# charger_v4.net
KiCad netlist of a schematic drawn in EAGLE
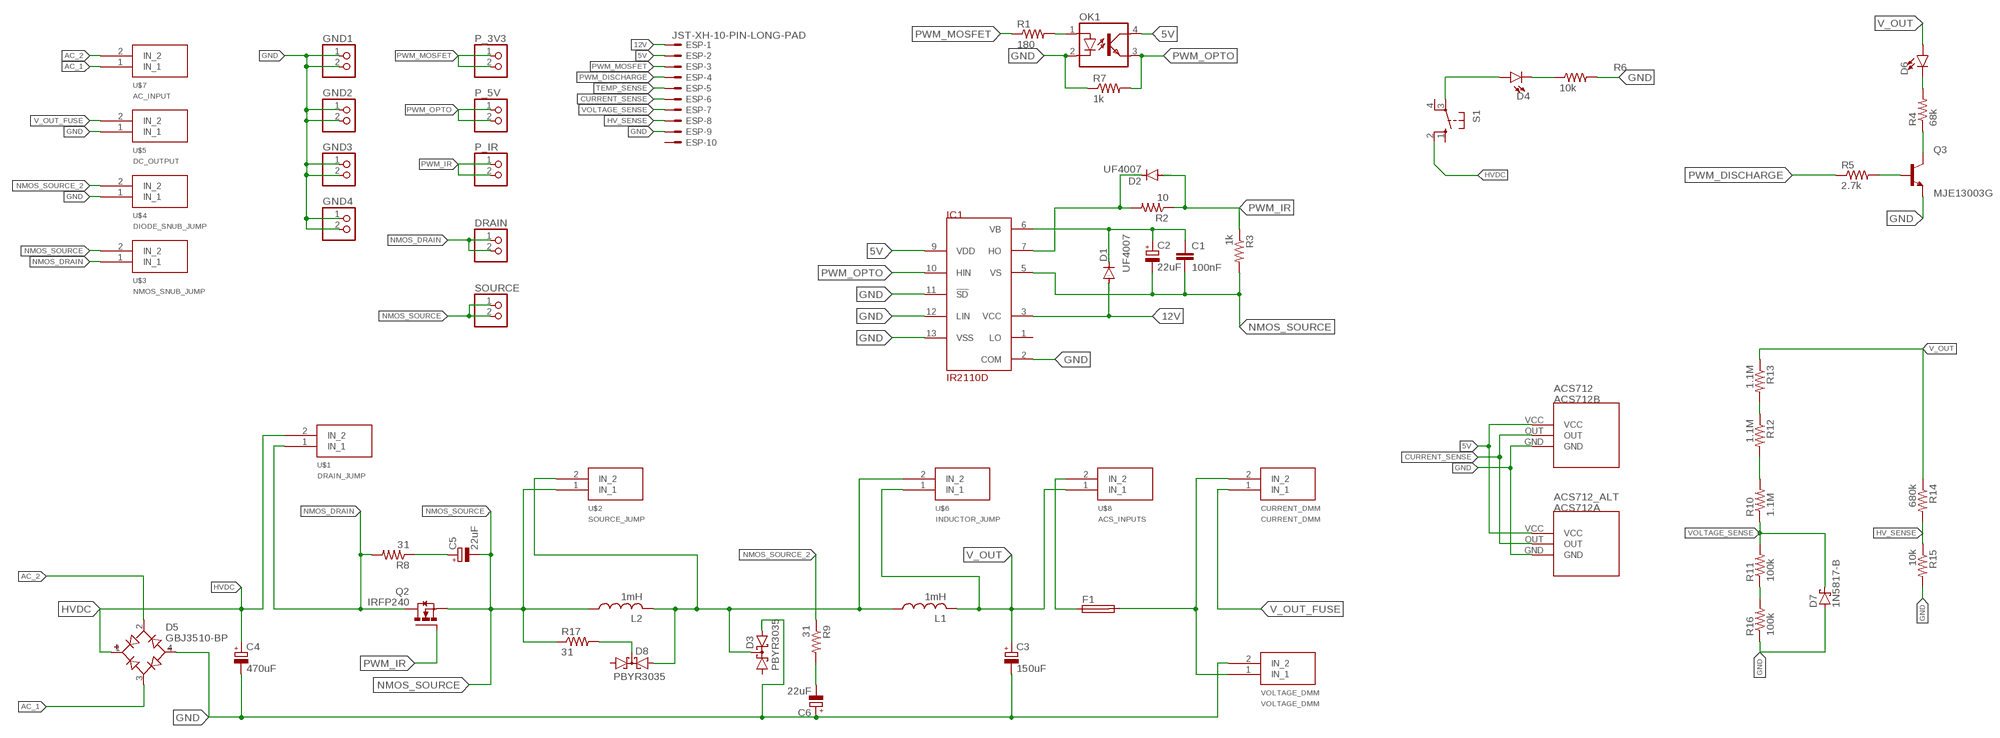
[diagram p0: schematic, sheet 1]

(export (version "E")
  (design (tool "Eeschema 10.0.6"))
  (components
    (comp (ref "ACS712")
      (value "ACS712B")
      (footprint "eagle-import:ACS712-2")
      (libsource (lib "eagle-import") (part "ACS712B"))
    )
    (comp (ref "ACS712_ALT")
      (value "ACS712A")
      (footprint "eagle-import:ACS712-1")
      (libsource (lib "eagle-import") (part "ACS712A"))
    )
    (comp (ref "C1")
      (value "100nF")
      (footprint "eagle-import:C025-025X050")
      (libsource (lib "eagle-import") (part "C-EU025-025X050"))
    )
    (comp (ref "C2")
      (value "22uF")
      (footprint "eagle-import:E2,5-6E")
      (libsource (lib "eagle-import") (part "CPOL-EUE2,5-6E"))
    )
    (comp (ref "C3")
      (value "150uF")
      (footprint "eagle-import:E7,5-18")
      (libsource (lib "eagle-import") (part "CPOL-EUE7.5-18"))
    )
    (comp (ref "C4")
      (value "470uF")
      (footprint "eagle-import:EB35D")
      (libsource (lib "eagle-import") (part "CPOL-EUE10-35"))
    )
    (comp (ref "C5")
      (value "22uF")
      (footprint "eagle-import:ETR4")
      (libsource (lib "eagle-import") (part "CPOL-EUETR4"))
    )
    (comp (ref "C6")
      (value "22uF")
      (footprint "eagle-import:ETR4")
      (libsource (lib "eagle-import") (part "CPOL-EUETR4"))
    )
    (comp (ref "CURRENT_DMM")
      (value "CURRENT_DMM")
      (footprint "eagle-import:TERMINAL_2P")
      (libsource (lib "eagle-import") (part "TERMINAL_2P"))
    )
    (comp (ref "D1")
      (value "UF4007")
      (footprint "eagle-import:DO34-7")
      (libsource (lib "eagle-import") (part "BAS15"))
    )
    (comp (ref "D2")
      (value "UF4007")
      (footprint "eagle-import:DO34-7")
      (libsource (lib "eagle-import") (part "BAS15"))
    )
    (comp (ref "D3")
      (value "PBYR3035")
      (footprint "eagle-import:SOT93S")
      (libsource (lib "eagle-import") (part "PBYR3035"))
    )
    (comp (ref "D4")
      (value "LED5MM")
      (footprint "eagle-import:LED_5MM")
      (libsource (lib "eagle-import") (part "LED5MM"))
    )
    (comp (ref "D5")
      (value "GBJ3510-BP")
      (footprint "eagle-import:DIOB_GBJ3510-BP")
      (fields (field (name "MF") "Micro Commercial"))
      (libsource (lib "eagle-import") (part "GBJ3510-BP"))
    )
    (comp (ref "D6")
      (value "LED5MM")
      (footprint "eagle-import:LED_5MM")
      (libsource (lib "eagle-import") (part "LED5MM"))
    )
    (comp (ref "D7")
      (value "1N5817-B")
      (footprint "eagle-import:DO41-7.6")
      (libsource (lib "eagle-import") (part "1N5817-B"))
    )
    (comp (ref "D8")
      (value "PBYR3035")
      (footprint "eagle-import:SOT93S")
      (libsource (lib "eagle-import") (part "PBYR3035"))
    )
    (comp (ref "DRAIN")
      (value "PINHD-1X2")
      (footprint "eagle-import:1X02")
      (libsource (lib "eagle-import") (part "PINHD-1X2"))
    )
    (comp (ref "ESP")
      (value "JST-XH-10-PIN-LONG-PAD")
      (footprint "eagle-import:JST-XH-10-PACKAGE-LONG-PAD")
      (libsource (lib "eagle-import") (part "JST-XH-10-PIN-LONG-PAD"))
    )
    (comp (ref "F1")
      (value "FUSEHOLDER")
      (footprint "eagle-import:FUSEHOLDER")
      (fields (field (name "MPN") "0031.7701.11"))
      (libsource (lib "eagle-import") (part "FUSEHOLDER"))
    )
    (comp (ref "GND1")
      (value "PINHD-1X2")
      (footprint "eagle-import:1X02")
      (libsource (lib "eagle-import") (part "PINHD-1X2"))
    )
    (comp (ref "GND2")
      (value "PINHD-1X2")
      (footprint "eagle-import:1X02")
      (libsource (lib "eagle-import") (part "PINHD-1X2"))
    )
    (comp (ref "GND3")
      (value "PINHD-1X2")
      (footprint "eagle-import:1X02")
      (libsource (lib "eagle-import") (part "PINHD-1X2"))
    )
    (comp (ref "GND4")
      (value "PINHD-1X2")
      (footprint "eagle-import:1X02")
      (libsource (lib "eagle-import") (part "PINHD-1X2"))
    )
    (comp (ref "IC1")
      (value "IR2110D")
      (footprint "eagle-import:DIL14")
      (libsource (lib "eagle-import") (part "IR2110D"))
    )
    (comp (ref "L1")
      (value "1mH")
      (footprint "eagle-import:TJ7-U1")
      (libsource (lib "eagle-import") (part "L-USTJ7-U1"))
    )
    (comp (ref "L2")
      (value "1mH")
      (footprint "eagle-import:TJ7-U1")
      (libsource (lib "eagle-import") (part "L-USTJ7-U1"))
    )
    (comp (ref "OK1")
      (value "SFH618A-5")
      (footprint "eagle-import:DIP4")
      (fields (field (name "MF") "VISHAY/TELEFUNKEN"))
      (libsource (lib "eagle-import") (part "SFH618?A-5"))
    )
    (comp (ref "P_3V3")
      (value "PINHD-1X2")
      (footprint "eagle-import:1X02")
      (libsource (lib "eagle-import") (part "PINHD-1X2"))
    )
    (comp (ref "P_5V")
      (value "PINHD-1X2")
      (footprint "eagle-import:1X02")
      (libsource (lib "eagle-import") (part "PINHD-1X2"))
    )
    (comp (ref "P_IR")
      (value "PINHD-1X2")
      (footprint "eagle-import:1X02")
      (libsource (lib "eagle-import") (part "PINHD-1X2"))
    )
    (comp (ref "Q2")
      (value "IRFP240")
      (footprint "eagle-import:TO247AC")
      (fields (field (name "MF") "Vishay Siliconix"))
      (libsource (lib "eagle-import") (part "IRFP240"))
    )
    (comp (ref "Q3")
      (value "MJE13003G")
      (footprint "eagle-import:TO229P780X300X1364-3")
      (fields (field (name "MF") "ON Semiconductor"))
      (libsource (lib "eagle-import") (part "MJE13003G"))
    )
    (comp (ref "R1")
      (value "180")
      (footprint "eagle-import:0204_7")
      (libsource (lib "eagle-import") (part "R-US_0204/7"))
    )
    (comp (ref "R2")
      (value "10")
      (footprint "eagle-import:0204_7")
      (libsource (lib "eagle-import") (part "R-US_0204/7"))
    )
    (comp (ref "R3")
      (value "1k")
      (footprint "eagle-import:0204_7")
      (libsource (lib "eagle-import") (part "R-US_0204/7"))
    )
    (comp (ref "R4")
      (value "68k")
      (footprint "eagle-import:0411_15")
      (libsource (lib "eagle-import") (part "R-US_0411/15"))
    )
    (comp (ref "R5")
      (value "2.7k")
      (footprint "eagle-import:0204_7")
      (libsource (lib "eagle-import") (part "R-US_0204/7"))
    )
    (comp (ref "R6")
      (value "10k")
      (footprint "eagle-import:0204_7")
      (libsource (lib "eagle-import") (part "R-US_0204/7"))
    )
    (comp (ref "R7")
      (value "1k")
      (footprint "eagle-import:0204_7")
      (libsource (lib "eagle-import") (part "R-US_0204/7"))
    )
    (comp (ref "R8")
      (value "31")
      (footprint "eagle-import:0411_15")
      (libsource (lib "eagle-import") (part "R-US_0411/15"))
    )
    (comp (ref "R9")
      (value "31")
      (footprint "eagle-import:0411_15")
      (libsource (lib "eagle-import") (part "R-US_0411/15"))
    )
    (comp (ref "R10")
      (value "1.1M")
      (footprint "eagle-import:R0805")
      (libsource (lib "eagle-import") (part "R-US_R0805"))
    )
    (comp (ref "R11")
      (value "100k")
      (footprint "eagle-import:R0805")
      (libsource (lib "eagle-import") (part "R-US_R0805"))
    )
    (comp (ref "R12")
      (value "1.1M")
      (footprint "eagle-import:R0805")
      (libsource (lib "eagle-import") (part "R-US_R0805"))
    )
    (comp (ref "R13")
      (value "1.1M")
      (footprint "eagle-import:R0805")
      (libsource (lib "eagle-import") (part "R-US_R0805"))
    )
    (comp (ref "R14")
      (value "680k")
      (footprint "eagle-import:0207_10")
      (libsource (lib "eagle-import") (part "R-US_0207/10"))
    )
    (comp (ref "R15")
      (value "10k")
      (footprint "eagle-import:0207_10")
      (libsource (lib "eagle-import") (part "R-US_0207/10"))
    )
    (comp (ref "R16")
      (value "100k")
      (footprint "eagle-import:R0805")
      (libsource (lib "eagle-import") (part "R-US_R0805"))
    )
    (comp (ref "R17")
      (value "31")
      (footprint "eagle-import:0411_15")
      (libsource (lib "eagle-import") (part "R-US_0411/15"))
    )
    (comp (ref "S1")
      (value "10-XX")
      (footprint "eagle-import:B3F-10XX")
      (fields (field (name "MPN") "B3F-1000"))
      (libsource (lib "eagle-import") (part "10-XX"))
    )
    (comp (ref "SOURCE")
      (value "PINHD-1X2")
      (footprint "eagle-import:1X02")
      (libsource (lib "eagle-import") (part "PINHD-1X2"))
    )
    (comp (ref "U$1")
      (value "DRAIN_JUMP")
      (footprint "eagle-import:TERMINAL_2P")
      (libsource (lib "eagle-import") (part "TERMINAL_2P"))
    )
    (comp (ref "U$2")
      (value "SOURCE_JUMP")
      (footprint "eagle-import:TERMINAL_2P")
      (libsource (lib "eagle-import") (part "TERMINAL_2P"))
    )
    (comp (ref "U$3")
      (value "NMOS_SNUB_JUMP")
      (footprint "eagle-import:TERMINAL_2P")
      (libsource (lib "eagle-import") (part "TERMINAL_2P"))
    )
    (comp (ref "U$4")
      (value "DIODE_SNUB_JUMP")
      (footprint "eagle-import:TERMINAL_2P")
      (libsource (lib "eagle-import") (part "TERMINAL_2P"))
    )
    (comp (ref "U$5")
      (value "DC_OUTPUT")
      (footprint "eagle-import:TERMINAL_2P")
      (libsource (lib "eagle-import") (part "TERMINAL_2P"))
    )
    (comp (ref "U$6")
      (value "INDUCTOR_JUMP")
      (footprint "eagle-import:TERMINAL_2P")
      (libsource (lib "eagle-import") (part "TERMINAL_2P"))
    )
    (comp (ref "U$7")
      (value "AC_INPUT")
      (footprint "eagle-import:TERMINAL_2P")
      (libsource (lib "eagle-import") (part "TERMINAL_2P"))
    )
    (comp (ref "U$8")
      (value "ACS_INPUTS")
      (footprint "eagle-import:TERMINAL_2P")
      (libsource (lib "eagle-import") (part "TERMINAL_2P"))
    )
    (comp (ref "VOLTAGE_DMM")
      (value "VOLTAGE_DMM")
      (footprint "eagle-import:TERMINAL_2P")
      (libsource (lib "eagle-import") (part "TERMINAL_2P"))
    )
  )
  (nets
    (net (code "1") (name "5V") (class "Default")
      (node (ref "ACS712") (pin "VCC") (pinfunction "VCC_VCC") (pintype "bidirectional"))
      (node (ref "ACS712_ALT") (pin "VCC") (pinfunction "VCC_VCC") (pintype "bidirectional"))
      (node (ref "ESP") (pin "2") (pinfunction "S_2") (pintype "passive"))
      (node (ref "IC1") (pin "9") (pinfunction "VDD_9") (pintype "power_in"))
      (node (ref "OK1") (pin "4") (pinfunction "COL_4") (pintype "passive"))
    )
    (net (code "2") (name "12V") (class "Default")
      (node (ref "D1") (pin "A") (pinfunction "A_A") (pintype "passive"))
      (node (ref "ESP") (pin "1") (pinfunction "S_1") (pintype "passive"))
      (node (ref "IC1") (pin "3") (pinfunction "VCC_3") (pintype "power_in"))
    )
    (net (code "3") (name "AC_1") (class "Default")
      (node (ref "D5") (pin "3") (pinfunction "AC2_3") (pintype "passive"))
      (node (ref "U$7") (pin "1") (pinfunction "IN_1_1") (pintype "bidirectional"))
    )
    (net (code "4") (name "AC_2") (class "Default")
      (node (ref "D5") (pin "2") (pinfunction "AC1_2") (pintype "passive"))
      (node (ref "U$7") (pin "2") (pinfunction "IN_2_2") (pintype "bidirectional"))
    )
    (net (code "5") (name "CURRENT_SENSE") (class "Default")
      (node (ref "ACS712") (pin "OUT") (pinfunction "OUT_OUT") (pintype "bidirectional"))
      (node (ref "ACS712_ALT") (pin "OUT") (pinfunction "OUT_OUT") (pintype "bidirectional"))
      (node (ref "ESP") (pin "6") (pinfunction "S_6") (pintype "passive"))
    )
    (net (code "6") (name "GND") (class "Default")
      (node (ref "ACS712") (pin "GND") (pinfunction "GND_GND") (pintype "bidirectional"))
      (node (ref "ACS712_ALT") (pin "GND") (pinfunction "GND_GND") (pintype "bidirectional"))
      (node (ref "C3") (pin "-") (pinfunction "-_-") (pintype "passive"))
      (node (ref "C4") (pin "-") (pinfunction "-_-") (pintype "passive"))
      (node (ref "C6") (pin "+") (pinfunction "+_+") (pintype "passive"))
      (node (ref "D3") (pin "A2") (pinfunction "A2_A2") (pintype "passive"))
      (node (ref "D5") (pin "4") (pinfunction "-_4") (pintype "passive"))
      (node (ref "D7") (pin "A") (pinfunction "A_A") (pintype "passive"))
      (node (ref "ESP") (pin "9") (pinfunction "S_9") (pintype "passive"))
      (node (ref "GND1") (pin "1") (pinfunction "1_1") (pintype "passive"))
      (node (ref "GND1") (pin "2") (pinfunction "2_2") (pintype "passive"))
      (node (ref "GND2") (pin "1") (pinfunction "1_1") (pintype "passive"))
      (node (ref "GND2") (pin "2") (pinfunction "2_2") (pintype "passive"))
      (node (ref "GND3") (pin "1") (pinfunction "1_1") (pintype "passive"))
      (node (ref "GND3") (pin "2") (pinfunction "2_2") (pintype "passive"))
      (node (ref "GND4") (pin "1") (pinfunction "1_1") (pintype "passive"))
      (node (ref "GND4") (pin "2") (pinfunction "2_2") (pintype "passive"))
      (node (ref "IC1") (pin "11") (pinfunction "~{SD}_11") (pintype "input"))
      (node (ref "IC1") (pin "12") (pinfunction "LIN_12") (pintype "input"))
      (node (ref "IC1") (pin "13") (pinfunction "VSS_13") (pintype "power_in"))
      (node (ref "IC1") (pin "2") (pinfunction "COM_2") (pintype "power_in"))
      (node (ref "OK1") (pin "2") (pinfunction "C_2") (pintype "passive"))
      (node (ref "Q3") (pin "3") (pinfunction "E_3") (pintype "passive"))
      (node (ref "R15") (pin "2") (pinfunction "2_2") (pintype "passive"))
      (node (ref "R16") (pin "1") (pinfunction "1_1") (pintype "passive"))
      (node (ref "R6") (pin "2") (pinfunction "2_2") (pintype "passive"))
      (node (ref "R7") (pin "1") (pinfunction "1_1") (pintype "passive"))
      (node (ref "U$4") (pin "1") (pinfunction "IN_1_1") (pintype "bidirectional"))
      (node (ref "U$5") (pin "1") (pinfunction "IN_1_1") (pintype "bidirectional"))
      (node (ref "VOLTAGE_DMM") (pin "2") (pinfunction "IN_2_2") (pintype "bidirectional"))
    )
    (net (code "7") (name "HVDC") (class "Default")
      (node (ref "C4") (pin "+") (pinfunction "+_+") (pintype "passive"))
      (node (ref "D5") (pin "1") (pinfunction "+_1") (pintype "passive"))
      (node (ref "S1") (pin "2") (pinfunction "S1_2") (pintype "passive"))
      (node (ref "U$1") (pin "2") (pinfunction "IN_2_2") (pintype "bidirectional"))
    )
    (net (code "8") (name "HV_SENSE") (class "Default")
      (node (ref "ESP") (pin "8") (pinfunction "S_8") (pintype "passive"))
      (node (ref "R14") (pin "2") (pinfunction "2_2") (pintype "passive"))
      (node (ref "R15") (pin "1") (pinfunction "1_1") (pintype "passive"))
    )
    (net (code "9") (name "NMOS_DRAIN") (class "Default")
      (node (ref "DRAIN") (pin "1") (pinfunction "1_1") (pintype "passive"))
      (node (ref "DRAIN") (pin "2") (pinfunction "2_2") (pintype "passive"))
      (node (ref "Q2") (pin "2") (pinfunction "D_2") (pintype "passive"))
      (node (ref "R8") (pin "2") (pinfunction "2_2") (pintype "passive"))
      (node (ref "U$1") (pin "1") (pinfunction "IN_1_1") (pintype "bidirectional"))
      (node (ref "U$3") (pin "1") (pinfunction "IN_1_1") (pintype "bidirectional"))
    )
    (net (code "10") (name "NMOS_SOURCE") (class "Default")
      (node (ref "C1") (pin "2") (pinfunction "2_2") (pintype "passive"))
      (node (ref "C2") (pin "-") (pinfunction "-_-") (pintype "passive"))
      (node (ref "C5") (pin "-") (pinfunction "-_-") (pintype "passive"))
      (node (ref "IC1") (pin "5") (pinfunction "VS_5") (pintype "power_in"))
      (node (ref "L2") (pin "1") (pinfunction "1_1") (pintype "passive"))
      (node (ref "Q2") (pin "3") (pinfunction "S_3") (pintype "passive"))
      (node (ref "R17") (pin "1") (pinfunction "1_1") (pintype "passive"))
      (node (ref "R3") (pin "2") (pinfunction "2_2") (pintype "passive"))
      (node (ref "SOURCE") (pin "1") (pinfunction "1_1") (pintype "passive"))
      (node (ref "SOURCE") (pin "2") (pinfunction "2_2") (pintype "passive"))
      (node (ref "U$2") (pin "1") (pinfunction "IN_1_1") (pintype "bidirectional"))
      (node (ref "U$3") (pin "2") (pinfunction "IN_2_2") (pintype "bidirectional"))
    )
    (net (code "11") (name "NMOS_SOURCE_2") (class "Default")
      (node (ref "D3") (pin "C") (pinfunction "C_C") (pintype "passive"))
      (node (ref "D8") (pin "A2") (pinfunction "A2_A2") (pintype "passive"))
      (node (ref "L1") (pin "1") (pinfunction "1_1") (pintype "passive"))
      (node (ref "L2") (pin "2") (pinfunction "2_2") (pintype "passive"))
      (node (ref "R9") (pin "1") (pinfunction "1_1") (pintype "passive"))
      (node (ref "U$2") (pin "2") (pinfunction "IN_2_2") (pintype "bidirectional"))
      (node (ref "U$4") (pin "2") (pinfunction "IN_2_2") (pintype "bidirectional"))
      (node (ref "U$6") (pin "2") (pinfunction "IN_2_2") (pintype "bidirectional"))
    )
    (net (code "12") (name "Net-(C5-Pad+)") (class "Default")
      (node (ref "C5") (pin "+") (pinfunction "+_+") (pintype "passive"))
      (node (ref "R8") (pin "1") (pinfunction "1_1") (pintype "passive"))
    )
    (net (code "13") (name "Net-(C6-Pad-)") (class "Default")
      (node (ref "C6") (pin "-") (pinfunction "-_-") (pintype "passive"))
      (node (ref "R9") (pin "2") (pinfunction "2_2") (pintype "passive"))
    )
    (net (code "14") (name "Net-(CURRENT_DMM-IN_2)") (class "Default")
      (node (ref "CURRENT_DMM") (pin "2") (pinfunction "IN_2_2") (pintype "bidirectional"))
      (node (ref "F1") (pin "2") (pinfunction "2_2") (pintype "passive"))
      (node (ref "VOLTAGE_DMM") (pin "1") (pinfunction "IN_1_1") (pintype "bidirectional"))
    )
    (net (code "15") (name "Net-(D4-C)") (class "Default")
      (node (ref "D4") (pin "K") (pinfunction "C_K") (pintype "passive"))
      (node (ref "R6") (pin "1") (pinfunction "1_1") (pintype "passive"))
    )
    (net (code "16") (name "Net-(D6-C)") (class "Default")
      (node (ref "D6") (pin "K") (pinfunction "C_K") (pintype "passive"))
      (node (ref "R4") (pin "2") (pinfunction "2_2") (pintype "passive"))
    )
    (net (code "17") (name "Net-(D8-PadC)") (class "Default")
      (node (ref "D8") (pin "C") (pinfunction "C_C") (pintype "passive"))
      (node (ref "R17") (pin "2") (pinfunction "2_2") (pintype "passive"))
    )
    (net (code "18") (name "Net-(IC1-HO)") (class "Default")
      (node (ref "D2") (pin "C") (pinfunction "C_C") (pintype "passive"))
      (node (ref "IC1") (pin "7") (pinfunction "HO_7") (pintype "output"))
      (node (ref "R2") (pin "2") (pinfunction "2_2") (pintype "passive"))
    )
    (net (code "19") (name "Net-(IC1-VB)") (class "Default")
      (node (ref "C1") (pin "1") (pinfunction "1_1") (pintype "passive"))
      (node (ref "C2") (pin "+") (pinfunction "+_+") (pintype "passive"))
      (node (ref "D1") (pin "C") (pinfunction "C_C") (pintype "passive"))
      (node (ref "IC1") (pin "6") (pinfunction "VB_6") (pintype "power_in"))
    )
    (net (code "20") (name "Net-(OK1-A)") (class "Default")
      (node (ref "OK1") (pin "1") (pinfunction "A_1") (pintype "passive"))
      (node (ref "R1") (pin "2") (pinfunction "2_2") (pintype "passive"))
    )
    (net (code "21") (name "Net-(Q3-B)") (class "Default")
      (node (ref "Q3") (pin "1") (pinfunction "B_1") (pintype "passive"))
      (node (ref "R5") (pin "2") (pinfunction "2_2") (pintype "passive"))
    )
    (net (code "22") (name "Net-(Q3-C)") (class "Default")
      (node (ref "Q3") (pin "2") (pinfunction "C_2") (pintype "passive"))
      (node (ref "R4") (pin "1") (pinfunction "1_1") (pintype "passive"))
    )
    (net (code "23") (name "Net-(R10-Pad2)") (class "Default")
      (node (ref "R10") (pin "2") (pinfunction "2_2") (pintype "passive"))
      (node (ref "R12") (pin "2") (pinfunction "2_2") (pintype "passive"))
    )
    (net (code "24") (name "Net-(R11-Pad1)") (class "Default")
      (node (ref "R11") (pin "1") (pinfunction "1_1") (pintype "passive"))
      (node (ref "R16") (pin "2") (pinfunction "2_2") (pintype "passive"))
    )
    (net (code "25") (name "Net-(R12-Pad1)") (class "Default")
      (node (ref "R12") (pin "1") (pinfunction "1_1") (pintype "passive"))
      (node (ref "R13") (pin "2") (pinfunction "2_2") (pintype "passive"))
    )
    (net (code "26") (name "Net-(S1-P)") (class "Default")
      (node (ref "D4") (pin "A") (pinfunction "A_A") (pintype "passive"))
      (node (ref "S1") (pin "3") (pinfunction "P_3") (pintype "passive"))
    )
    (net (code "27") (name "Net-(U$8-IN_2)") (class "Default")
      (node (ref "F1") (pin "1") (pinfunction "1_1") (pintype "passive"))
      (node (ref "U$8") (pin "2") (pinfunction "IN_2_2") (pintype "bidirectional"))
    )
    (net (code "28") (name "PWM_DISCHARGE") (class "Default")
      (node (ref "ESP") (pin "4") (pinfunction "S_4") (pintype "passive"))
      (node (ref "R5") (pin "1") (pinfunction "1_1") (pintype "passive"))
    )
    (net (code "29") (name "PWM_IR") (class "Default")
      (node (ref "D2") (pin "A") (pinfunction "A_A") (pintype "passive"))
      (node (ref "P_IR") (pin "1") (pinfunction "1_1") (pintype "passive"))
      (node (ref "P_IR") (pin "2") (pinfunction "2_2") (pintype "passive"))
      (node (ref "Q2") (pin "1") (pinfunction "G_1") (pintype "passive"))
      (node (ref "R2") (pin "1") (pinfunction "1_1") (pintype "passive"))
      (node (ref "R3") (pin "1") (pinfunction "1_1") (pintype "passive"))
    )
    (net (code "30") (name "PWM_MOSFET") (class "Default")
      (node (ref "ESP") (pin "3") (pinfunction "S_3") (pintype "passive"))
      (node (ref "P_3V3") (pin "1") (pinfunction "1_1") (pintype "passive"))
      (node (ref "P_3V3") (pin "2") (pinfunction "2_2") (pintype "passive"))
      (node (ref "R1") (pin "1") (pinfunction "1_1") (pintype "passive"))
    )
    (net (code "31") (name "PWM_OPTO") (class "Default")
      (node (ref "IC1") (pin "10") (pinfunction "HIN_10") (pintype "input"))
      (node (ref "OK1") (pin "3") (pinfunction "EMIT_3") (pintype "passive"))
      (node (ref "P_5V") (pin "1") (pinfunction "1_1") (pintype "passive"))
      (node (ref "P_5V") (pin "2") (pinfunction "2_2") (pintype "passive"))
      (node (ref "R7") (pin "2") (pinfunction "2_2") (pintype "passive"))
    )
    (net (code "32") (name "TEMP_SENSE") (class "Default")
      (node (ref "ESP") (pin "5") (pinfunction "S_5") (pintype "passive"))
    )
    (net (code "33") (name "VOLTAGE_SENSE") (class "Default")
      (node (ref "D7") (pin "C") (pinfunction "C_C") (pintype "passive"))
      (node (ref "ESP") (pin "7") (pinfunction "S_7") (pintype "passive"))
      (node (ref "R10") (pin "1") (pinfunction "1_1") (pintype "passive"))
      (node (ref "R11") (pin "2") (pinfunction "2_2") (pintype "passive"))
    )
    (net (code "34") (name "V_OUT") (class "Default")
      (node (ref "C3") (pin "+") (pinfunction "+_+") (pintype "passive"))
      (node (ref "D6") (pin "A") (pinfunction "A_A") (pintype "passive"))
      (node (ref "L1") (pin "2") (pinfunction "2_2") (pintype "passive"))
      (node (ref "R13") (pin "1") (pinfunction "1_1") (pintype "passive"))
      (node (ref "R14") (pin "1") (pinfunction "1_1") (pintype "passive"))
      (node (ref "U$6") (pin "1") (pinfunction "IN_1_1") (pintype "bidirectional"))
      (node (ref "U$8") (pin "1") (pinfunction "IN_1_1") (pintype "bidirectional"))
    )
    (net (code "35") (name "V_OUT_FUSE") (class "Default")
      (node (ref "CURRENT_DMM") (pin "1") (pinfunction "IN_1_1") (pintype "bidirectional"))
      (node (ref "U$5") (pin "2") (pinfunction "IN_2_2") (pintype "bidirectional"))
    )
    (net (code "36") (name "unconnected-(D3-PadA1)") (class "Default")
      (node (ref "D3") (pin "A1") (pinfunction "A1_A1") (pintype "passive"))
    )
    (net (code "37") (name "unconnected-(D8-PadA1)") (class "Default")
      (node (ref "D8") (pin "A1") (pinfunction "A1_A1") (pintype "passive"))
    )
    (net (code "38") (name "unconnected-(ESPB-S-Pad10)") (class "Default")
      (node (ref "ESP") (pin "10") (pinfunction "S_10") (pintype "passive"))
    )
    (net (code "39") (name "unconnected-(IC1-LO-Pad1)") (class "Default")
      (node (ref "IC1") (pin "1") (pinfunction "LO_1") (pintype "output"))
    )
    (net (code "40") (name "unconnected-(S1-P1-Pad4)") (class "Default")
      (node (ref "S1") (pin "4") (pinfunction "P1_4") (pintype "passive"))
    )
    (net (code "41") (name "unconnected-(S1-S-Pad1)") (class "Default")
      (node (ref "S1") (pin "1") (pinfunction "S_1") (pintype "passive"))
    )
  )
)
